# EBR01_1.net
KiCad netlist of a schematic drawn in EAGLE
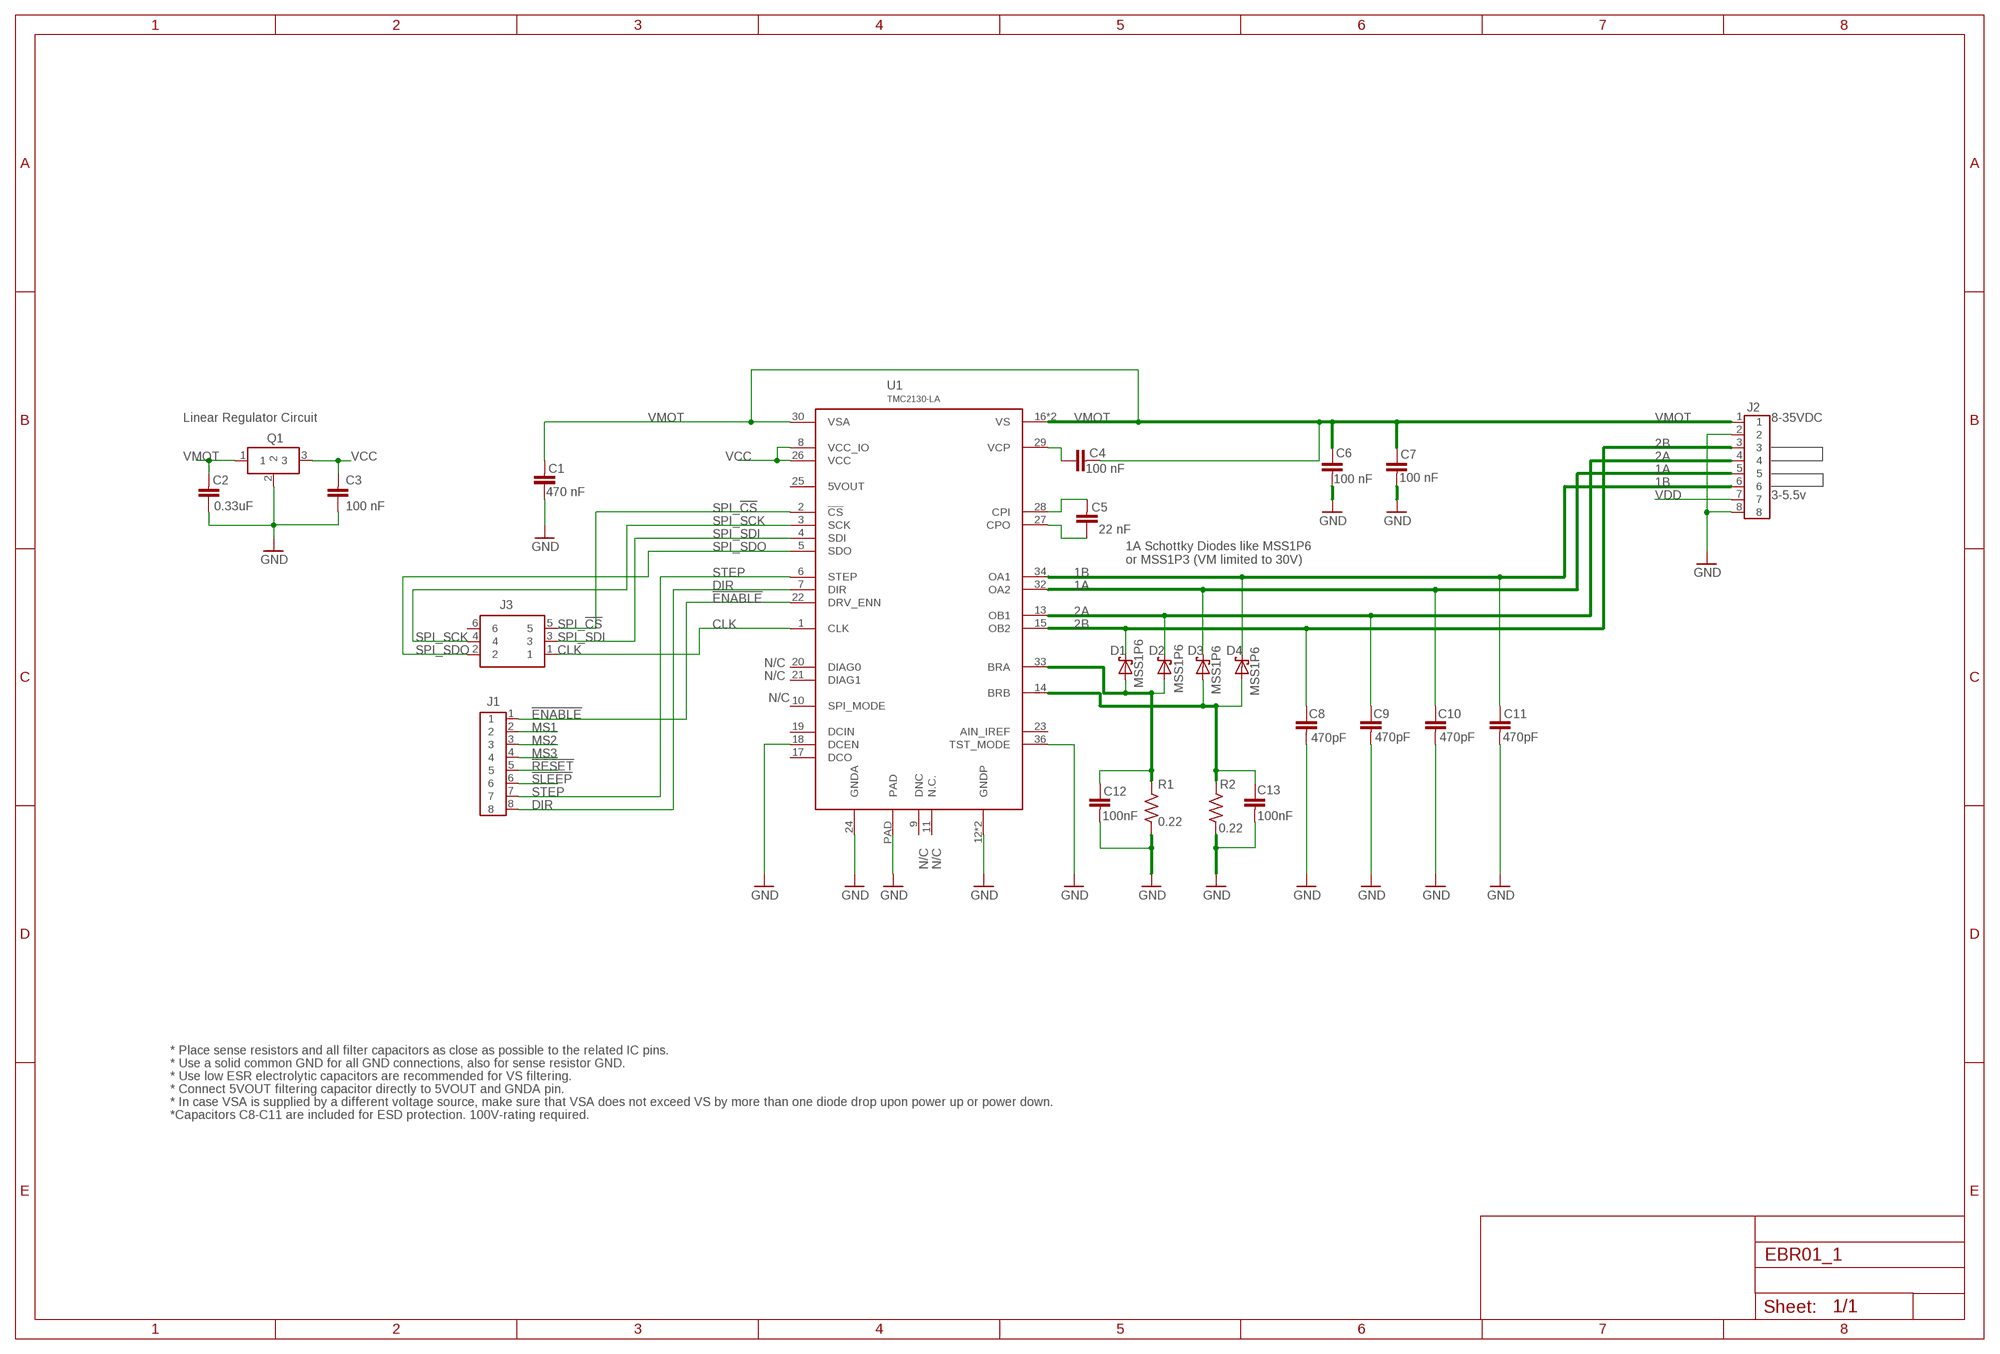
[diagram p0: schematic, sheet 1]

(export (version "E")
  (design (tool "Eeschema 10.0.6"))
  (components
    (comp (ref "C1")
      (value "470 nF")
      (footprint "eagle-import:C0603")
      (libsource (lib "eagle-import") (part "CPL-CAP-X7R-0603-0.47UF-35V"))
    )
    (comp (ref "C2")
      (value "0.33uF")
      (footprint "eagle-import:C0603")
      (libsource (lib "eagle-import") (part "CPL-CAP-X7R-0603-0.33UF-35V"))
    )
    (comp (ref "C3")
      (value "100 nF")
      (footprint "eagle-import:C0603")
      (libsource (lib "eagle-import") (part "CPL-CAP-X7R-0603-100NF-50V"))
    )
    (comp (ref "C4")
      (value "100 nF")
      (footprint "eagle-import:C0603")
      (libsource (lib "eagle-import") (part "CPL-CAP-X7R-0603-100NF-100V"))
    )
    (comp (ref "C5")
      (value "22 nF")
      (footprint "eagle-import:C0603")
      (libsource (lib "eagle-import") (part "CPL-CAP-X7R-0603-22NF-50V{dblquote}"))
    )
    (comp (ref "C6")
      (value "100 nF")
      (footprint "eagle-import:C0603")
      (libsource (lib "eagle-import") (part "CPL-CAP-X7R-0603-100NF-100V"))
    )
    (comp (ref "C7")
      (value "100 nF")
      (footprint "eagle-import:C0603")
      (libsource (lib "eagle-import") (part "CPL-CAP-X7R-0603-100NF-100V"))
    )
    (comp (ref "C8")
      (value "470pF")
      (footprint "eagle-import:C0603")
      (libsource (lib "eagle-import") (part "CPL-CAP-X7R-0603-470PF-100V"))
    )
    (comp (ref "C9")
      (value "470pF")
      (footprint "eagle-import:C0603")
      (libsource (lib "eagle-import") (part "CPL-CAP-X7R-0603-470PF-100V"))
    )
    (comp (ref "C10")
      (value "470pF")
      (footprint "eagle-import:C0603")
      (libsource (lib "eagle-import") (part "CPL-CAP-X7R-0603-470PF-100V"))
    )
    (comp (ref "C11")
      (value "470pF")
      (footprint "eagle-import:C0603")
      (libsource (lib "eagle-import") (part "CPL-CAP-X7R-0603-470PF-100V"))
    )
    (comp (ref "C12")
      (value "100nF")
      (footprint "eagle-import:C0603")
      (libsource (lib "eagle-import") (part "CPL-CAP-X7R-0603-100NF-50V"))
    )
    (comp (ref "C13")
      (value "100nF")
      (footprint "eagle-import:C0603")
      (libsource (lib "eagle-import") (part "CPL-CAP-X7R-0603-100NF-50V"))
    )
    (comp (ref "D1")
      (value "MSS1P6")
      (footprint "eagle-import:MICRO-SMP")
      (libsource (lib "eagle-import") (part "CPL-DIO-MSS1P6-MICROSMP"))
    )
    (comp (ref "D2")
      (value "MSS1P6")
      (footprint "eagle-import:MICRO-SMP")
      (libsource (lib "eagle-import") (part "CPL-DIO-MSS1P6-MICROSMP"))
    )
    (comp (ref "D3")
      (value "MSS1P6")
      (footprint "eagle-import:MICRO-SMP")
      (libsource (lib "eagle-import") (part "CPL-DIO-MSS1P6-MICROSMP"))
    )
    (comp (ref "D4")
      (value "MSS1P6")
      (footprint "eagle-import:MICRO-SMP")
      (libsource (lib "eagle-import") (part "CPL-DIO-MSS1P6-MICROSMP"))
    )
    (comp (ref "J1")
      (value "CPL-CON-HEADER-0.1IN-8P-M")
      (footprint "eagle-import:CON-HDR-8POS-MALE")
      (libsource (lib "eagle-import") (part "CPL-CON-HEADER-0.1IN-8P-M"))
    )
    (comp (ref "J2")
      (value "CPL-CON-HEADER-0.1IN-8P-M")
      (footprint "eagle-import:CON-HDR-8POS-MALE")
      (libsource (lib "eagle-import") (part "CPL-CON-HEADER-0.1IN-8P-M"))
    )
    (comp (ref "J3")
      (value "CPL-CON-HEADER-0.1IN-2X3P-M")
      (footprint "eagle-import:CON-HDR-2X3P")
      (libsource (lib "eagle-import") (part "CPL-CON-HEADER-0.1IN-2X3P-M"))
    )
    (comp (ref "Q1")
      (value "CPL-REG-LIN-5V-0.1A")
      (footprint "eagle-import:SOT-89")
      (libsource (lib "eagle-import") (part "CPL-REG-LIN-5V-0.1A"))
    )
    (comp (ref "R1")
      (value "0.22")
      (footprint "eagle-import:R1206")
      (libsource (lib "eagle-import") (part "CPL-RES-1206-0.22-0.5W"))
    )
    (comp (ref "R2")
      (value "0.22")
      (footprint "eagle-import:R1206")
      (libsource (lib "eagle-import") (part "CPL-RES-1206-0.22-0.5W"))
    )
    (comp (ref "U1")
      (value "TMC2130-LA")
      (footprint "eagle-import:QFN36-(5X6)")
      (libsource (lib "eagle-import") (part "CPL-MDR-2PHSTEPPER"))
    )
  )
  (nets
    (net (code "1") (name "/1A") (class "Default")
      (node (ref "C10") (pin "1") (pinfunction "1_1") (pintype "passive"))
      (node (ref "D3") (pin "NEG") (pinfunction "C_NEG") (pintype "passive"))
      (node (ref "J2") (pin "5") (pinfunction "5_5") (pintype "passive"))
      (node (ref "U1") (pin "32") (pinfunction "OA2_32") (pintype "bidirectional"))
    )
    (net (code "2") (name "/1B") (class "Default")
      (node (ref "C11") (pin "1") (pinfunction "1_1") (pintype "passive"))
      (node (ref "D4") (pin "NEG") (pinfunction "C_NEG") (pintype "passive"))
      (node (ref "J2") (pin "6") (pinfunction "6_6") (pintype "passive"))
      (node (ref "U1") (pin "34") (pinfunction "OA1_34") (pintype "bidirectional"))
    )
    (net (code "3") (name "/2A") (class "Default")
      (node (ref "C9") (pin "1") (pinfunction "1_1") (pintype "passive"))
      (node (ref "D2") (pin "NEG") (pinfunction "C_NEG") (pintype "passive"))
      (node (ref "J2") (pin "4") (pinfunction "4_4") (pintype "passive"))
      (node (ref "U1") (pin "13") (pinfunction "OB1_13") (pintype "bidirectional"))
    )
    (net (code "4") (name "/2B") (class "Default")
      (node (ref "C8") (pin "1") (pinfunction "1_1") (pintype "passive"))
      (node (ref "D1") (pin "NEG") (pinfunction "C_NEG") (pintype "passive"))
      (node (ref "J2") (pin "3") (pinfunction "3_3") (pintype "passive"))
      (node (ref "U1") (pin "15") (pinfunction "OB2_15") (pintype "bidirectional"))
    )
    (net (code "5") (name "/CLK") (class "Default")
      (node (ref "J3") (pin "1") (pinfunction "1_1") (pintype "passive"))
      (node (ref "U1") (pin "1") (pinfunction "CLK_1") (pintype "bidirectional"))
    )
    (net (code "6") (name "/DIR") (class "Default")
      (node (ref "J1") (pin "8") (pinfunction "8_8") (pintype "passive"))
      (node (ref "U1") (pin "7") (pinfunction "DIR_7") (pintype "bidirectional"))
    )
    (net (code "7") (name "/MS1") (class "Default")
      (node (ref "J1") (pin "2") (pinfunction "2_2") (pintype "passive"))
    )
    (net (code "8") (name "/MS2") (class "Default")
      (node (ref "J1") (pin "3") (pinfunction "3_3") (pintype "passive"))
    )
    (net (code "9") (name "/MS3") (class "Default")
      (node (ref "J1") (pin "4") (pinfunction "4_4") (pintype "passive"))
    )
    (net (code "10") (name "/SPI_SCK") (class "Default")
      (node (ref "J3") (pin "4") (pinfunction "4_4") (pintype "passive"))
      (node (ref "U1") (pin "3") (pinfunction "SCK_3") (pintype "bidirectional"))
    )
    (net (code "11") (name "/SPI_SDI") (class "Default")
      (node (ref "J3") (pin "3") (pinfunction "3_3") (pintype "passive"))
      (node (ref "U1") (pin "4") (pinfunction "SDI_4") (pintype "bidirectional"))
    )
    (net (code "12") (name "/SPI_SDO") (class "Default")
      (node (ref "J3") (pin "2") (pinfunction "2_2") (pintype "passive"))
      (node (ref "U1") (pin "5") (pinfunction "SDO_5") (pintype "bidirectional"))
    )
    (net (code "13") (name "/SPI_~{CS}") (class "Default")
      (node (ref "J3") (pin "5") (pinfunction "5_5") (pintype "passive"))
      (node (ref "U1") (pin "2") (pinfunction "~{CS}_2") (pintype "bidirectional"))
    )
    (net (code "14") (name "/STEP") (class "Default")
      (node (ref "J1") (pin "7") (pinfunction "7_7") (pintype "passive"))
      (node (ref "U1") (pin "6") (pinfunction "STEP_6") (pintype "bidirectional"))
    )
    (net (code "15") (name "/VCC") (class "Default")
      (node (ref "C3") (pin "2") (pinfunction "2_2") (pintype "passive"))
      (node (ref "Q1") (pin "3") (pinfunction "3_3") (pintype "passive"))
      (node (ref "U1") (pin "26") (pinfunction "VCC_26") (pintype "bidirectional"))
      (node (ref "U1") (pin "8") (pinfunction "VCC_IO_8") (pintype "bidirectional"))
    )
    (net (code "16") (name "/VDD") (class "Default")
      (node (ref "J2") (pin "7") (pinfunction "7_7") (pintype "passive"))
    )
    (net (code "17") (name "/VMOT") (class "Default")
      (node (ref "C1") (pin "2") (pinfunction "2_2") (pintype "passive"))
      (node (ref "C2") (pin "2") (pinfunction "2_2") (pintype "passive"))
      (node (ref "C4") (pin "2") (pinfunction "2_2") (pintype "passive"))
      (node (ref "C6") (pin "1") (pinfunction "1_1") (pintype "passive"))
      (node (ref "C7") (pin "1") (pinfunction "1_1") (pintype "passive"))
      (node (ref "J2") (pin "1") (pinfunction "1_1") (pintype "passive"))
      (node (ref "Q1") (pin "1") (pinfunction "1_1") (pintype "passive"))
      (node (ref "U1") (pin "16") (pinfunction "VS_16") (pintype "bidirectional"))
      (node (ref "U1") (pin "30") (pinfunction "VSA_30") (pintype "bidirectional"))
      (node (ref "U1") (pin "31") (pinfunction "VS_31") (pintype "bidirectional"))
    )
    (net (code "18") (name "/~{ENABLE}") (class "Default")
      (node (ref "J1") (pin "1") (pinfunction "1_1") (pintype "passive"))
      (node (ref "U1") (pin "22") (pinfunction "DRV_ENN_22") (pintype "bidirectional"))
    )
    (net (code "19") (name "/~{RESET}") (class "Default")
      (node (ref "J1") (pin "5") (pinfunction "5_5") (pintype "passive"))
    )
    (net (code "20") (name "/~{SLEEP}") (class "Default")
      (node (ref "J1") (pin "6") (pinfunction "6_6") (pintype "passive"))
    )
    (net (code "21") (name "GND") (class "Default")
      (node (ref "C1") (pin "1") (pinfunction "1_1") (pintype "passive"))
      (node (ref "C10") (pin "2") (pinfunction "2_2") (pintype "passive"))
      (node (ref "C11") (pin "2") (pinfunction "2_2") (pintype "passive"))
      (node (ref "C12") (pin "2") (pinfunction "2_2") (pintype "passive"))
      (node (ref "C13") (pin "2") (pinfunction "2_2") (pintype "passive"))
      (node (ref "C2") (pin "1") (pinfunction "1_1") (pintype "passive"))
      (node (ref "C3") (pin "1") (pinfunction "1_1") (pintype "passive"))
      (node (ref "C6") (pin "2") (pinfunction "2_2") (pintype "passive"))
      (node (ref "C7") (pin "2") (pinfunction "2_2") (pintype "passive"))
      (node (ref "C8") (pin "2") (pinfunction "2_2") (pintype "passive"))
      (node (ref "C9") (pin "2") (pinfunction "2_2") (pintype "passive"))
      (node (ref "J2") (pin "2") (pinfunction "2_2") (pintype "passive"))
      (node (ref "J2") (pin "8") (pinfunction "8_8") (pintype "passive"))
      (node (ref "Q1") (pin "2") (pinfunction "2_2") (pintype "passive"))
      (node (ref "R1") (pin "1") (pinfunction "1_1") (pintype "passive"))
      (node (ref "R2") (pin "1") (pinfunction "1_1") (pintype "passive"))
      (node (ref "U1") (pin "12") (pinfunction "GNDP_12") (pintype "bidirectional"))
      (node (ref "U1") (pin "18") (pinfunction "DCEN_18") (pintype "bidirectional"))
      (node (ref "U1") (pin "24") (pinfunction "GNDA_24") (pintype "bidirectional"))
      (node (ref "U1") (pin "35") (pinfunction "GNDP_35") (pintype "bidirectional"))
      (node (ref "U1") (pin "36") (pinfunction "TST_MODE_36") (pintype "bidirectional"))
      (node (ref "U1") (pin "PAD") (pinfunction "PAD_PAD") (pintype "bidirectional"))
    )
    (net (code "22") (name "Net-(D1-A)") (class "Default")
      (node (ref "C12") (pin "1") (pinfunction "1_1") (pintype "passive"))
      (node (ref "D1") (pin "POS") (pinfunction "A_POS") (pintype "passive"))
      (node (ref "D2") (pin "POS") (pinfunction "A_POS") (pintype "passive"))
      (node (ref "R1") (pin "2") (pinfunction "2_2") (pintype "passive"))
      (node (ref "U1") (pin "33") (pinfunction "BRA_33") (pintype "bidirectional"))
    )
    (net (code "23") (name "Net-(D3-A)") (class "Default")
      (node (ref "C13") (pin "1") (pinfunction "1_1") (pintype "passive"))
      (node (ref "D3") (pin "POS") (pinfunction "A_POS") (pintype "passive"))
      (node (ref "D4") (pin "POS") (pinfunction "A_POS") (pintype "passive"))
      (node (ref "R2") (pin "2") (pinfunction "2_2") (pintype "passive"))
      (node (ref "U1") (pin "14") (pinfunction "BRB_14") (pintype "bidirectional"))
    )
    (net (code "24") (name "Net-(U1-CPI)") (class "Default")
      (node (ref "C5") (pin "2") (pinfunction "2_2") (pintype "passive"))
      (node (ref "U1") (pin "28") (pinfunction "CPI_28") (pintype "bidirectional"))
    )
    (net (code "25") (name "Net-(U1-CPO)") (class "Default")
      (node (ref "C5") (pin "1") (pinfunction "1_1") (pintype "passive"))
      (node (ref "U1") (pin "27") (pinfunction "CPO_27") (pintype "bidirectional"))
    )
    (net (code "26") (name "Net-(U1-VCP)") (class "Default")
      (node (ref "C4") (pin "1") (pinfunction "1_1") (pintype "passive"))
      (node (ref "U1") (pin "29") (pinfunction "VCP_29") (pintype "bidirectional"))
    )
    (net (code "27") (name "unconnected-(J3-Pad6)") (class "Default")
      (node (ref "J3") (pin "6") (pinfunction "6_6") (pintype "passive"))
    )
    (net (code "28") (name "unconnected-(U1-5VOUT-Pad25)") (class "Default")
      (node (ref "U1") (pin "25") (pinfunction "5VOUT_25") (pintype "bidirectional"))
    )
    (net (code "29") (name "unconnected-(U1-AIN_IREF-Pad23)") (class "Default")
      (node (ref "U1") (pin "23") (pinfunction "AIN_IREF_23") (pintype "bidirectional"))
    )
    (net (code "30") (name "unconnected-(U1-DCIN-Pad19)") (class "Default")
      (node (ref "U1") (pin "19") (pinfunction "DCIN_19") (pintype "bidirectional"))
    )
    (net (code "31") (name "unconnected-(U1-DCO-Pad17)") (class "Default")
      (node (ref "U1") (pin "17") (pinfunction "DCO_17") (pintype "bidirectional"))
    )
    (net (code "32") (name "unconnected-(U1-DIAG0-Pad20)") (class "Default")
      (node (ref "U1") (pin "20") (pinfunction "DIAG0_20") (pintype "bidirectional"))
    )
    (net (code "33") (name "unconnected-(U1-DIAG1-Pad21)") (class "Default")
      (node (ref "U1") (pin "21") (pinfunction "DIAG1_21") (pintype "bidirectional"))
    )
    (net (code "34") (name "unconnected-(U1-DNC-Pad9)") (class "Default")
      (node (ref "U1") (pin "9") (pinfunction "DNC_9") (pintype "bidirectional"))
    )
    (net (code "35") (name "unconnected-(U1-N.C.-Pad11)") (class "Default")
      (node (ref "U1") (pin "11") (pinfunction "N.C._11") (pintype "bidirectional"))
    )
    (net (code "36") (name "unconnected-(U1-SPI_MODE-Pad10)") (class "Default")
      (node (ref "U1") (pin "10") (pinfunction "SPI_MODE_10") (pintype "bidirectional"))
    )
  )
)
